# OSO-MISC-21-012_Sensor_Watch_Testpoints_.net
KiCad netlist of a schematic drawn in EAGLE
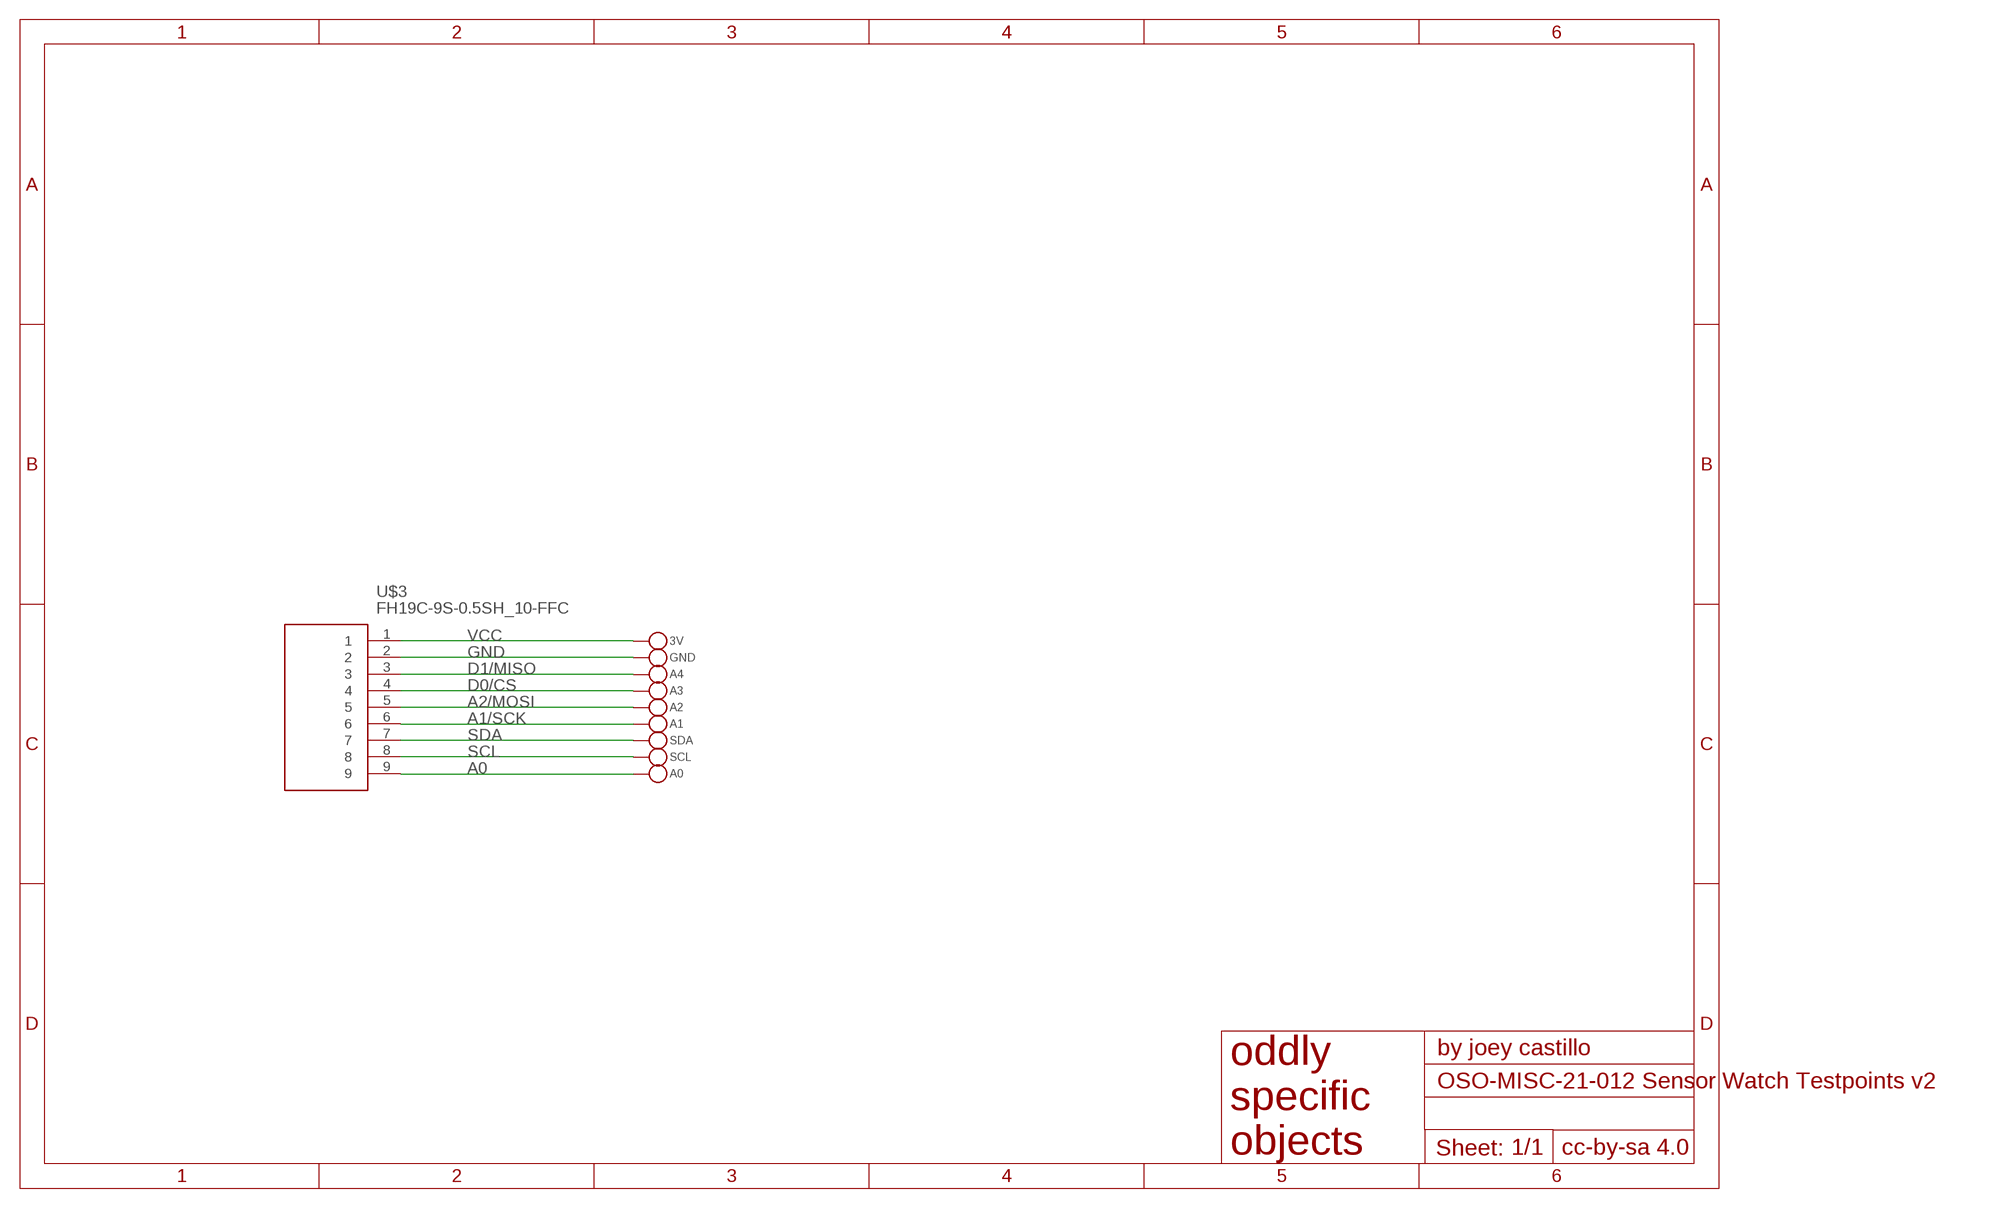
[diagram p0: schematic, sheet 1]

(export (version "E")
  (design (tool "Eeschema 10.0.6"))
  (components
    (comp (ref "3V")
      (value "MICROBUILDER_TESTPOINT1.5X2.0MM_NOCREAM")
      (footprint "eagle-import:MICROBUILDER_PAD-1.5X2.0")
      (libsource (lib "eagle-import") (part "MICROBUILDER_TESTPOINT1.5X2.0MM_NOCREAM"))
    )
    (comp (ref "A0")
      (value "MICROBUILDER_TESTPOINT1.5X2.0MM_NOCREAM")
      (footprint "eagle-import:MICROBUILDER_PAD-1.5X2.0")
      (libsource (lib "eagle-import") (part "MICROBUILDER_TESTPOINT1.5X2.0MM_NOCREAM"))
    )
    (comp (ref "A1")
      (value "MICROBUILDER_TESTPOINT1.5X2.0MM_NOCREAM")
      (footprint "eagle-import:MICROBUILDER_PAD-1.5X2.0")
      (libsource (lib "eagle-import") (part "MICROBUILDER_TESTPOINT1.5X2.0MM_NOCREAM"))
    )
    (comp (ref "A2")
      (value "MICROBUILDER_TESTPOINT1.5X2.0MM_NOCREAM")
      (footprint "eagle-import:MICROBUILDER_PAD-1.5X2.0")
      (libsource (lib "eagle-import") (part "MICROBUILDER_TESTPOINT1.5X2.0MM_NOCREAM"))
    )
    (comp (ref "A3")
      (value "MICROBUILDER_TESTPOINT1.5X2.0MM_NOCREAM")
      (footprint "eagle-import:MICROBUILDER_PAD-1.5X2.0")
      (libsource (lib "eagle-import") (part "MICROBUILDER_TESTPOINT1.5X2.0MM_NOCREAM"))
    )
    (comp (ref "A4")
      (value "MICROBUILDER_TESTPOINT1.5X2.0MM_NOCREAM")
      (footprint "eagle-import:MICROBUILDER_PAD-1.5X2.0")
      (libsource (lib "eagle-import") (part "MICROBUILDER_TESTPOINT1.5X2.0MM_NOCREAM"))
    )
    (comp (ref "GND")
      (value "MICROBUILDER_TESTPOINT1.5X2.0MM_NOCREAM")
      (footprint "eagle-import:MICROBUILDER_PAD-1.5X2.0")
      (libsource (lib "eagle-import") (part "MICROBUILDER_TESTPOINT1.5X2.0MM_NOCREAM"))
    )
    (comp (ref "SCL")
      (value "MICROBUILDER_TESTPOINT1.5X2.0MM_NOCREAM")
      (footprint "eagle-import:MICROBUILDER_PAD-1.5X2.0")
      (libsource (lib "eagle-import") (part "MICROBUILDER_TESTPOINT1.5X2.0MM_NOCREAM"))
    )
    (comp (ref "SDA")
      (value "MICROBUILDER_TESTPOINT1.5X2.0MM_NOCREAM")
      (footprint "eagle-import:MICROBUILDER_PAD-1.5X2.0")
      (libsource (lib "eagle-import") (part "MICROBUILDER_TESTPOINT1.5X2.0MM_NOCREAM"))
    )
    (comp (ref "U$3")
      (value "FH19C-9S-0.5SH_10-FFC")
      (footprint "eagle-import:FH19C9S05SH10-FFC")
      (libsource (lib "eagle-import") (part "FH19C-9S-0.5SH_10-FFC"))
    )
  )
  (nets
    (net (code "1") (name "/A0") (class "Default")
      (node (ref "A0") (pin "P$1") (pinfunction "P$1_P$1") (pintype "bidirectional"))
      (node (ref "U$3") (pin "9") (pinfunction "9_9") (pintype "bidirectional"))
    )
    (net (code "2") (name "/A1{slash}SCK") (class "Default")
      (node (ref "A1") (pin "P$1") (pinfunction "P$1_P$1") (pintype "bidirectional"))
      (node (ref "U$3") (pin "6") (pinfunction "6_6") (pintype "bidirectional"))
    )
    (net (code "3") (name "/A2{slash}MOSI") (class "Default")
      (node (ref "A2") (pin "P$1") (pinfunction "P$1_P$1") (pintype "bidirectional"))
      (node (ref "U$3") (pin "5") (pinfunction "5_5") (pintype "bidirectional"))
    )
    (net (code "4") (name "/D0{slash}CS") (class "Default")
      (node (ref "A3") (pin "P$1") (pinfunction "P$1_P$1") (pintype "bidirectional"))
      (node (ref "U$3") (pin "4") (pinfunction "4_4") (pintype "bidirectional"))
    )
    (net (code "5") (name "/D1{slash}MISO") (class "Default")
      (node (ref "A4") (pin "P$1") (pinfunction "P$1_P$1") (pintype "bidirectional"))
      (node (ref "U$3") (pin "3") (pinfunction "3_3") (pintype "bidirectional"))
    )
    (net (code "6") (name "/GND") (class "Default")
      (node (ref "GND") (pin "P$1") (pinfunction "P$1_P$1") (pintype "bidirectional"))
      (node (ref "U$3") (pin "2") (pinfunction "2_2") (pintype "bidirectional"))
    )
    (net (code "7") (name "/SCL") (class "Default")
      (node (ref "SCL") (pin "P$1") (pinfunction "P$1_P$1") (pintype "bidirectional"))
      (node (ref "U$3") (pin "8") (pinfunction "8_8") (pintype "bidirectional"))
    )
    (net (code "8") (name "/SDA") (class "Default")
      (node (ref "SDA") (pin "P$1") (pinfunction "P$1_P$1") (pintype "bidirectional"))
      (node (ref "U$3") (pin "7") (pinfunction "7_7") (pintype "bidirectional"))
    )
    (net (code "9") (name "/VCC") (class "Default")
      (node (ref "3V") (pin "P$1") (pinfunction "P$1_P$1") (pintype "bidirectional"))
      (node (ref "U$3") (pin "1") (pinfunction "1_1") (pintype "bidirectional"))
    )
  )
)
